# Ventilation.net
KiCad netlist of a schematic drawn in EAGLE
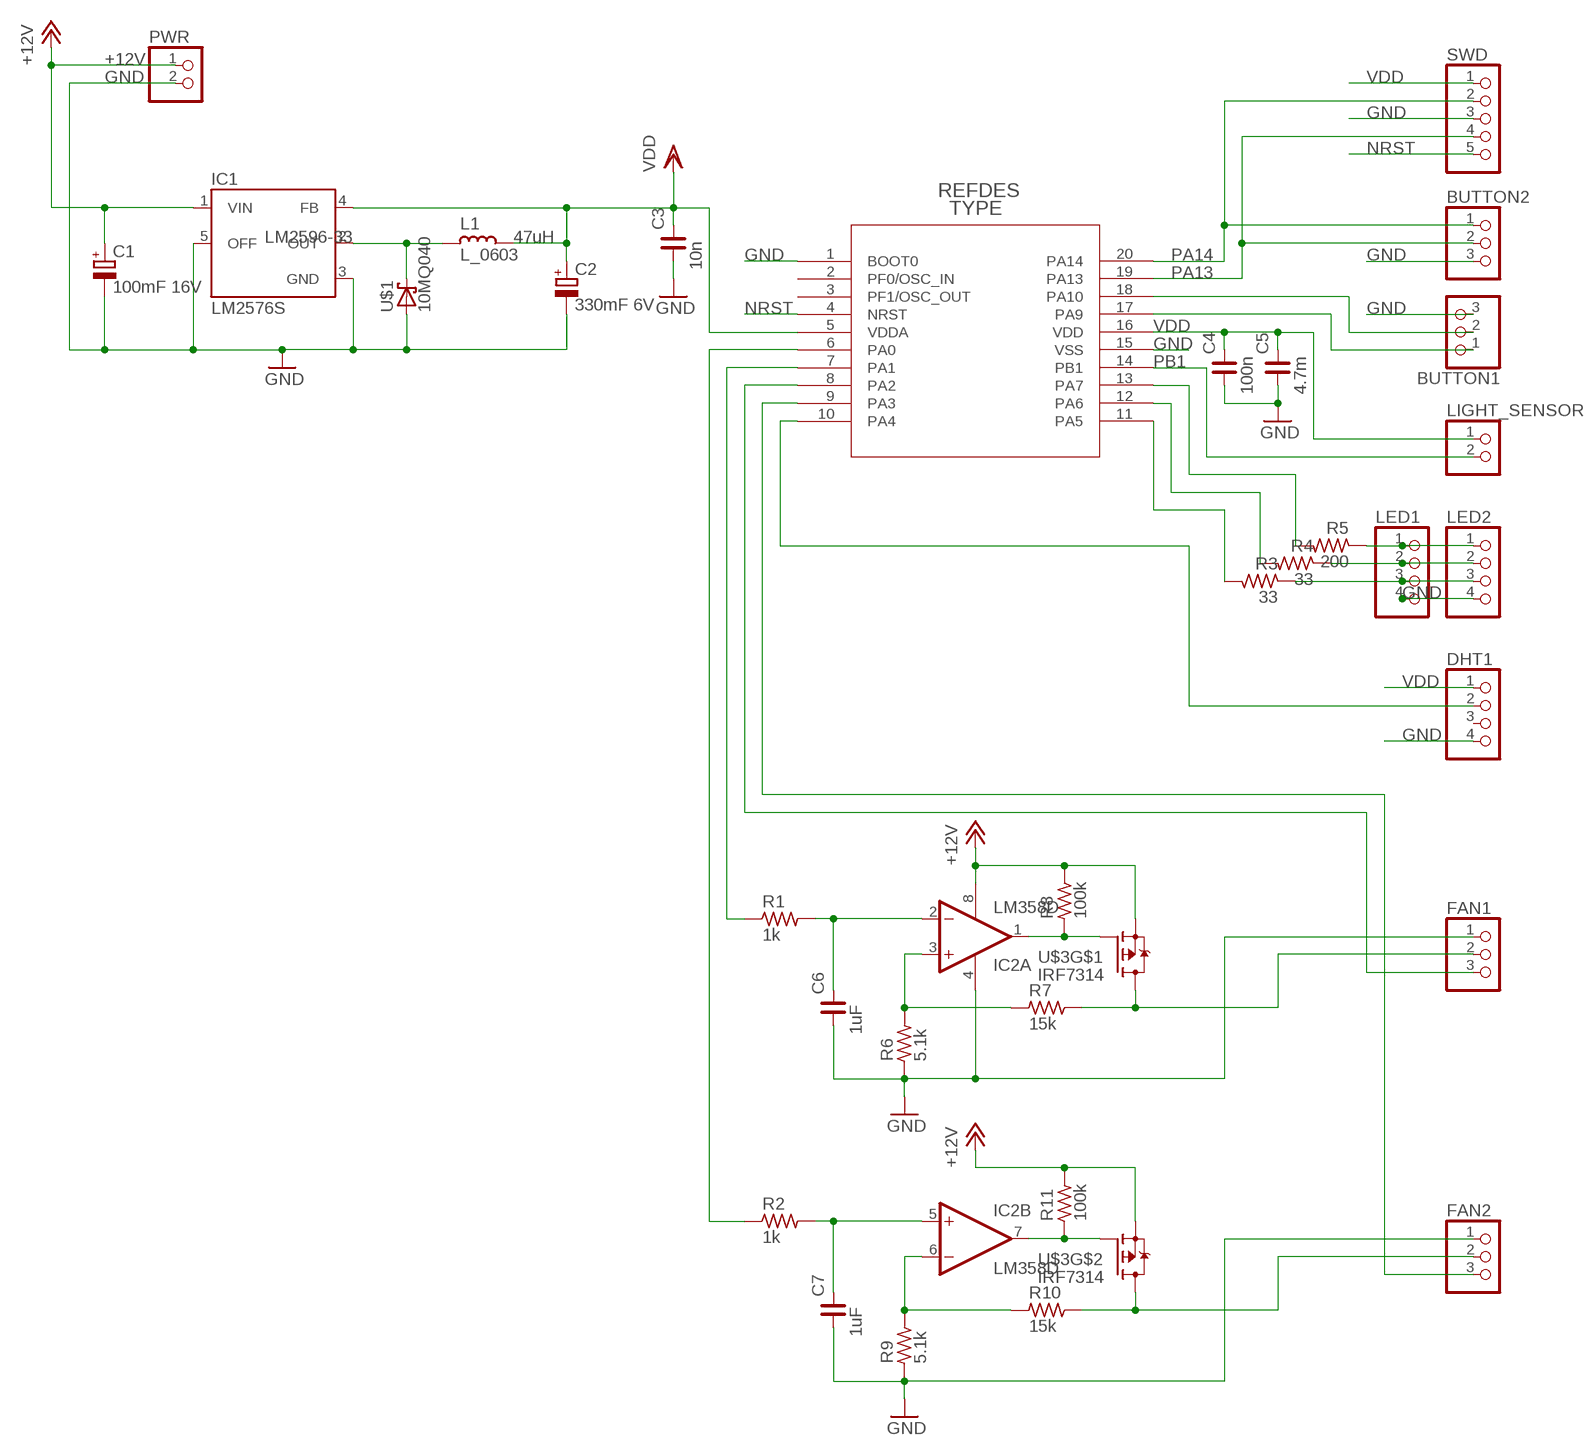
[diagram p0: schematic, sheet 1]

(export (version "E")
  (design (tool "Eeschema 10.0.6"))
  (components
    (comp (ref "BUTTON1")
      (value "PINHD-1X03_2.54-S")
      (footprint "eagle-import:1X03-S")
      (libsource (lib "eagle-import") (part "PINHD-1X03_2.54-S"))
    )
    (comp (ref "BUTTON2")
      (value "PINHD-1X03_2.54-S")
      (footprint "eagle-import:1X03-S")
      (libsource (lib "eagle-import") (part "PINHD-1X03_2.54-S"))
    )
    (comp (ref "C1")
      (value "100mF 16V")
      (footprint "eagle-import:SMC_D")
      (libsource (lib "eagle-import") (part "CPOL-EUSMCD"))
    )
    (comp (ref "C2")
      (value "330mF 6V")
      (footprint "eagle-import:SMC_D")
      (libsource (lib "eagle-import") (part "CPOL-EUSMCD"))
    )
    (comp (ref "C3")
      (value "10n")
      (footprint "eagle-import:C1206")
      (libsource (lib "eagle-import") (part "C_1206"))
    )
    (comp (ref "C4")
      (value "100n")
      (footprint "eagle-import:C1206")
      (libsource (lib "eagle-import") (part "C_1206"))
    )
    (comp (ref "C5")
      (value "4.7m")
      (footprint "eagle-import:C1206")
      (libsource (lib "eagle-import") (part "C_1206"))
    )
    (comp (ref "C6")
      (value "1uF")
      (footprint "eagle-import:C0805")
      (libsource (lib "eagle-import") (part "C_0805"))
    )
    (comp (ref "C7")
      (value "1uF")
      (footprint "eagle-import:C0805")
      (libsource (lib "eagle-import") (part "C_0805"))
    )
    (comp (ref "DHT1")
      (value "PINHD-1X04_2.54-S")
      (footprint "eagle-import:1X04-S")
      (libsource (lib "eagle-import") (part "PINHD-1X04_2.54-S"))
    )
    (comp (ref "FAN1")
      (value "PINHD-1X03_2.54-S")
      (footprint "eagle-import:1X03-S")
      (libsource (lib "eagle-import") (part "PINHD-1X03_2.54-S"))
    )
    (comp (ref "FAN2")
      (value "PINHD-1X03_2.54-S")
      (footprint "eagle-import:1X03-S")
      (libsource (lib "eagle-import") (part "PINHD-1X03_2.54-S"))
    )
    (comp (ref "IC1")
      (value "LM2576S")
      (footprint "eagle-import:TO263-5")
      (libsource (lib "eagle-import") (part "LM2576S"))
    )
    (comp (ref "IC2")
      (value "LM358D")
      (footprint "eagle-import:SO08")
      (libsource (lib "eagle-import") (part "LM358D"))
    )
    (comp (ref "L1")
      (value "L_0603")
      (footprint "eagle-import:L0603")
      (fields (field (name "LCN0603T-47NJ-N") "47uH"))
      (libsource (lib "eagle-import") (part "L_0603"))
    )
    (comp (ref "LED1")
      (value "PINHD-1X04_2.54-S")
      (footprint "eagle-import:1X04-S")
      (libsource (lib "eagle-import") (part "PINHD-1X04_2.54-S"))
    )
    (comp (ref "LED2")
      (value "PINHD-1X04_2.54-S")
      (footprint "eagle-import:1X04-S")
      (libsource (lib "eagle-import") (part "PINHD-1X04_2.54-S"))
    )
    (comp (ref "LIGHT_SENSOR")
      (value "PINHD-1X02_2.54-S")
      (footprint "eagle-import:1X02-S")
      (libsource (lib "eagle-import") (part "PINHD-1X02_2.54-S"))
    )
    (comp (ref "PWR")
      (value "PINHD-1X02_2.54-S")
      (footprint "eagle-import:1X02-S")
      (libsource (lib "eagle-import") (part "PINHD-1X02_2.54-S"))
    )
    (comp (ref "R1")
      (value "1k")
      (footprint "eagle-import:R0805")
      (libsource (lib "eagle-import") (part "R_0805"))
    )
    (comp (ref "R2")
      (value "1k")
      (footprint "eagle-import:R0805")
      (libsource (lib "eagle-import") (part "R_0805"))
    )
    (comp (ref "R3")
      (value "33")
      (footprint "eagle-import:R0805")
      (libsource (lib "eagle-import") (part "R_0805"))
    )
    (comp (ref "R4")
      (value "33")
      (footprint "eagle-import:R0805")
      (libsource (lib "eagle-import") (part "R_0805"))
    )
    (comp (ref "R5")
      (value "200")
      (footprint "eagle-import:R0805")
      (libsource (lib "eagle-import") (part "R_0805"))
    )
    (comp (ref "R6")
      (value "5.1k")
      (footprint "eagle-import:R0805")
      (libsource (lib "eagle-import") (part "R_0805"))
    )
    (comp (ref "R7")
      (value "15k")
      (footprint "eagle-import:R0805")
      (libsource (lib "eagle-import") (part "R_0805"))
    )
    (comp (ref "R8")
      (value "100k")
      (footprint "eagle-import:R0805")
      (libsource (lib "eagle-import") (part "R_0805"))
    )
    (comp (ref "R9")
      (value "5.1k")
      (footprint "eagle-import:R0805")
      (libsource (lib "eagle-import") (part "R_0805"))
    )
    (comp (ref "R10")
      (value "15k")
      (footprint "eagle-import:R0805")
      (libsource (lib "eagle-import") (part "R_0805"))
    )
    (comp (ref "R11")
      (value "100k")
      (footprint "eagle-import:R0805")
      (libsource (lib "eagle-import") (part "R_0805"))
    )
    (comp (ref "SWD")
      (value "PINHD-1X05_2.54-S")
      (footprint "eagle-import:1X05-S")
      (libsource (lib "eagle-import") (part "PINHD-1X05_2.54-S"))
    )
    (comp (ref "U$1")
      (value "10MQ040")
      (footprint "eagle-import:SMA")
      (libsource (lib "eagle-import") (part "10MQ040"))
    )
    (comp (ref "U$2")
      (value "STM32F050F4P6")
      (footprint "eagle-import:TSSOP20")
      (libsource (lib "eagle-import") (part "STM32F050F4P6"))
    )
    (comp (ref "U$3")
      (value "IRF7314")
      (footprint "eagle-import:SO-8")
      (libsource (lib "eagle-import") (part "IRF7314"))
    )
  )
  (nets
    (net (code "1") (name "+12V") (class "Default")
      (node (ref "C1") (pin "+") (pinfunction "+_+") (pintype "passive"))
      (node (ref "IC1") (pin "1") (pinfunction "VIN_1") (pintype "power_in"))
      (node (ref "IC2") (pin "8") (pinfunction "V+_8") (pintype "power_in"))
      (node (ref "PWR") (pin "1") (pinfunction "1_1") (pintype "passive"))
      (node (ref "R11") (pin "2") (pinfunction "2_2") (pintype "passive"))
      (node (ref "R8") (pin "2") (pinfunction "2_2") (pintype "passive"))
      (node (ref "U$3") (pin "1") (pinfunction "S_1") (pintype "passive"))
      (node (ref "U$3") (pin "3") (pinfunction "S_3") (pintype "passive"))
    )
    (net (code "2") (name "/NRST") (class "Default")
      (node (ref "SWD") (pin "5") (pinfunction "5_5") (pintype "passive"))
      (node (ref "U$2") (pin "4") (pinfunction "NRST_4") (pintype "passive"))
    )
    (net (code "3") (name "/PA13") (class "Default")
      (node (ref "BUTTON2") (pin "2") (pinfunction "2_2") (pintype "passive"))
      (node (ref "SWD") (pin "4") (pinfunction "4_4") (pintype "passive"))
      (node (ref "U$2") (pin "19") (pinfunction "PA13_19") (pintype "passive"))
    )
    (net (code "4") (name "/PA14") (class "Default")
      (node (ref "BUTTON2") (pin "1") (pinfunction "1_1") (pintype "passive"))
      (node (ref "SWD") (pin "2") (pinfunction "2_2") (pintype "passive"))
      (node (ref "U$2") (pin "20") (pinfunction "PA14_20") (pintype "passive"))
    )
    (net (code "5") (name "/PB1") (class "Default")
      (node (ref "LIGHT_SENSOR") (pin "2") (pinfunction "2_2") (pintype "passive"))
      (node (ref "U$2") (pin "14") (pinfunction "PB1_14") (pintype "passive"))
    )
    (net (code "6") (name "GND") (class "Default")
      (node (ref "BUTTON1") (pin "3") (pinfunction "3_3") (pintype "passive"))
      (node (ref "BUTTON2") (pin "3") (pinfunction "3_3") (pintype "passive"))
      (node (ref "C1") (pin "-") (pinfunction "-_-") (pintype "passive"))
      (node (ref "C2") (pin "-") (pinfunction "-_-") (pintype "passive"))
      (node (ref "C3") (pin "1") (pinfunction "1_1") (pintype "passive"))
      (node (ref "C4") (pin "1") (pinfunction "1_1") (pintype "passive"))
      (node (ref "C5") (pin "1") (pinfunction "1_1") (pintype "passive"))
      (node (ref "C6") (pin "1") (pinfunction "1_1") (pintype "passive"))
      (node (ref "C7") (pin "1") (pinfunction "1_1") (pintype "passive"))
      (node (ref "DHT1") (pin "4") (pinfunction "4_4") (pintype "passive"))
      (node (ref "FAN1") (pin "1") (pinfunction "1_1") (pintype "passive"))
      (node (ref "FAN2") (pin "1") (pinfunction "1_1") (pintype "passive"))
      (node (ref "IC1") (pin "3") (pinfunction "GND_3") (pintype "power_in"))
      (node (ref "IC1") (pin "5") (pinfunction "OFF_5") (pintype "input"))
      (node (ref "IC2") (pin "4") (pinfunction "V-_4") (pintype "power_in"))
      (node (ref "LED1") (pin "4") (pinfunction "4_4") (pintype "passive"))
      (node (ref "LED2") (pin "4") (pinfunction "4_4") (pintype "passive"))
      (node (ref "PWR") (pin "2") (pinfunction "2_2") (pintype "passive"))
      (node (ref "R6") (pin "1") (pinfunction "1_1") (pintype "passive"))
      (node (ref "R9") (pin "1") (pinfunction "1_1") (pintype "passive"))
      (node (ref "SWD") (pin "3") (pinfunction "3_3") (pintype "passive"))
      (node (ref "U$1") (pin "A") (pinfunction "A_A") (pintype "passive"))
      (node (ref "U$2") (pin "1") (pinfunction "BOOT0_1") (pintype "passive"))
      (node (ref "U$2") (pin "15") (pinfunction "VSS_15") (pintype "passive"))
    )
    (net (code "7") (name "Net-(FAN1-Pad2)") (class "Default")
      (node (ref "FAN1") (pin "2") (pinfunction "2_2") (pintype "passive"))
      (node (ref "R7") (pin "2") (pinfunction "2_2") (pintype "passive"))
      (node (ref "U$3") (pin "7") (pinfunction "D_7") (pintype "passive"))
      (node (ref "U$3") (pin "8") (pinfunction "D_8") (pintype "passive"))
    )
    (net (code "8") (name "Net-(FAN2-Pad2)") (class "Default")
      (node (ref "FAN2") (pin "2") (pinfunction "2_2") (pintype "passive"))
      (node (ref "R10") (pin "2") (pinfunction "2_2") (pintype "passive"))
      (node (ref "U$3") (pin "5") (pinfunction "D_5") (pintype "passive"))
      (node (ref "U$3") (pin "6") (pinfunction "D_6") (pintype "passive"))
    )
    (net (code "9") (name "Net-(IC1-OUT)") (class "Default")
      (node (ref "IC1") (pin "2") (pinfunction "OUT_2") (pintype "output"))
      (node (ref "L1") (pin "2") (pinfunction "2_2") (pintype "passive"))
      (node (ref "U$1") (pin "C") (pinfunction "C_C") (pintype "passive"))
    )
    (net (code "10") (name "Net-(IC2A-+IN)") (class "Default")
      (node (ref "IC2") (pin "3") (pinfunction "+IN_3") (pintype "input"))
      (node (ref "R6") (pin "2") (pinfunction "2_2") (pintype "passive"))
      (node (ref "R7") (pin "1") (pinfunction "1_1") (pintype "passive"))
    )
    (net (code "11") (name "Net-(IC2A--IN)") (class "Default")
      (node (ref "C6") (pin "2") (pinfunction "2_2") (pintype "passive"))
      (node (ref "IC2") (pin "2") (pinfunction "-IN_2") (pintype "input"))
      (node (ref "R1") (pin "2") (pinfunction "2_2") (pintype "passive"))
    )
    (net (code "12") (name "Net-(IC2A-OUT)") (class "Default")
      (node (ref "IC2") (pin "1") (pinfunction "OUT_1") (pintype "output"))
      (node (ref "R8") (pin "1") (pinfunction "1_1") (pintype "passive"))
      (node (ref "U$3") (pin "2") (pinfunction "G_2") (pintype "passive"))
    )
    (net (code "13") (name "Net-(IC2B-+IN)") (class "Default")
      (node (ref "C7") (pin "2") (pinfunction "2_2") (pintype "passive"))
      (node (ref "IC2") (pin "5") (pinfunction "+IN_5") (pintype "input"))
      (node (ref "R2") (pin "2") (pinfunction "2_2") (pintype "passive"))
    )
    (net (code "14") (name "Net-(IC2B--IN)") (class "Default")
      (node (ref "IC2") (pin "6") (pinfunction "-IN_6") (pintype "input"))
      (node (ref "R10") (pin "1") (pinfunction "1_1") (pintype "passive"))
      (node (ref "R9") (pin "2") (pinfunction "2_2") (pintype "passive"))
    )
    (net (code "15") (name "Net-(IC2B-OUT)") (class "Default")
      (node (ref "IC2") (pin "7") (pinfunction "OUT_7") (pintype "output"))
      (node (ref "R11") (pin "1") (pinfunction "1_1") (pintype "passive"))
      (node (ref "U$3") (pin "4") (pinfunction "G_4") (pintype "passive"))
    )
    (net (code "16") (name "Net-(LED1-Pad1)") (class "Default")
      (node (ref "LED1") (pin "1") (pinfunction "1_1") (pintype "passive"))
      (node (ref "LED2") (pin "1") (pinfunction "1_1") (pintype "passive"))
      (node (ref "R5") (pin "1") (pinfunction "1_1") (pintype "passive"))
    )
    (net (code "17") (name "Net-(LED1-Pad2)") (class "Default")
      (node (ref "LED1") (pin "2") (pinfunction "2_2") (pintype "passive"))
      (node (ref "LED2") (pin "2") (pinfunction "2_2") (pintype "passive"))
      (node (ref "R4") (pin "1") (pinfunction "1_1") (pintype "passive"))
    )
    (net (code "18") (name "Net-(LED1-Pad3)") (class "Default")
      (node (ref "LED1") (pin "3") (pinfunction "3_3") (pintype "passive"))
      (node (ref "LED2") (pin "3") (pinfunction "3_3") (pintype "passive"))
      (node (ref "R3") (pin "1") (pinfunction "1_1") (pintype "passive"))
    )
    (net (code "19") (name "Net-(U$2-PA0)") (class "Default")
      (node (ref "R2") (pin "1") (pinfunction "1_1") (pintype "passive"))
      (node (ref "U$2") (pin "6") (pinfunction "PA0_6") (pintype "passive"))
    )
    (net (code "20") (name "Net-(U$2-PA1)") (class "Default")
      (node (ref "R1") (pin "1") (pinfunction "1_1") (pintype "passive"))
      (node (ref "U$2") (pin "7") (pinfunction "PA1_7") (pintype "passive"))
    )
    (net (code "21") (name "Net-(U$2-PA2)") (class "Default")
      (node (ref "FAN1") (pin "3") (pinfunction "3_3") (pintype "passive"))
      (node (ref "U$2") (pin "8") (pinfunction "PA2_8") (pintype "passive"))
    )
    (net (code "22") (name "Net-(U$2-PA3)") (class "Default")
      (node (ref "FAN2") (pin "3") (pinfunction "3_3") (pintype "passive"))
      (node (ref "U$2") (pin "9") (pinfunction "PA3_9") (pintype "passive"))
    )
    (net (code "23") (name "Net-(U$2-PA4)") (class "Default")
      (node (ref "DHT1") (pin "2") (pinfunction "2_2") (pintype "passive"))
      (node (ref "U$2") (pin "10") (pinfunction "PA4_10") (pintype "passive"))
    )
    (net (code "24") (name "Net-(U$2-PA5)") (class "Default")
      (node (ref "R3") (pin "2") (pinfunction "2_2") (pintype "passive"))
      (node (ref "U$2") (pin "11") (pinfunction "PA5_11") (pintype "passive"))
    )
    (net (code "25") (name "Net-(U$2-PA6)") (class "Default")
      (node (ref "R4") (pin "2") (pinfunction "2_2") (pintype "passive"))
      (node (ref "U$2") (pin "12") (pinfunction "PA6_12") (pintype "passive"))
    )
    (net (code "26") (name "Net-(U$2-PA7)") (class "Default")
      (node (ref "R5") (pin "2") (pinfunction "2_2") (pintype "passive"))
      (node (ref "U$2") (pin "13") (pinfunction "PA7_13") (pintype "passive"))
    )
    (net (code "27") (name "Net-(U$2-PA9)") (class "Default")
      (node (ref "BUTTON1") (pin "1") (pinfunction "1_1") (pintype "passive"))
      (node (ref "U$2") (pin "17") (pinfunction "PA9_17") (pintype "passive"))
    )
    (net (code "28") (name "Net-(U$2-PA10)") (class "Default")
      (node (ref "BUTTON1") (pin "2") (pinfunction "2_2") (pintype "passive"))
      (node (ref "U$2") (pin "18") (pinfunction "PA10_18") (pintype "passive"))
    )
    (net (code "29") (name "VDD") (class "Default")
      (node (ref "C2") (pin "+") (pinfunction "+_+") (pintype "passive"))
      (node (ref "C3") (pin "2") (pinfunction "2_2") (pintype "passive"))
      (node (ref "C4") (pin "2") (pinfunction "2_2") (pintype "passive"))
      (node (ref "C5") (pin "2") (pinfunction "2_2") (pintype "passive"))
      (node (ref "DHT1") (pin "1") (pinfunction "1_1") (pintype "passive"))
      (node (ref "IC1") (pin "4") (pinfunction "FB_4") (pintype "input"))
      (node (ref "L1") (pin "1") (pinfunction "1_1") (pintype "passive"))
      (node (ref "LIGHT_SENSOR") (pin "1") (pinfunction "1_1") (pintype "passive"))
      (node (ref "SWD") (pin "1") (pinfunction "1_1") (pintype "passive"))
      (node (ref "U$2") (pin "16") (pinfunction "VDD_16") (pintype "passive"))
      (node (ref "U$2") (pin "5") (pinfunction "VDDA_5") (pintype "passive"))
    )
    (net (code "30") (name "unconnected-(DHT1-Pad3)") (class "Default")
      (node (ref "DHT1") (pin "3") (pinfunction "3_3") (pintype "passive"))
    )
    (net (code "31") (name "unconnected-(U$2-PF0{slash}OSC_IN-Pad2)") (class "Default")
      (node (ref "U$2") (pin "2") (pinfunction "PF0/OSC_IN_2") (pintype "passive"))
    )
    (net (code "32") (name "unconnected-(U$2-PF1{slash}OSC_OUT-Pad3)") (class "Default")
      (node (ref "U$2") (pin "3") (pinfunction "PF1/OSC_OUT_3") (pintype "passive"))
    )
  )
)
